# Mech_Interface_Starboard.net
KiCad netlist of a schematic drawn in Altium Designer
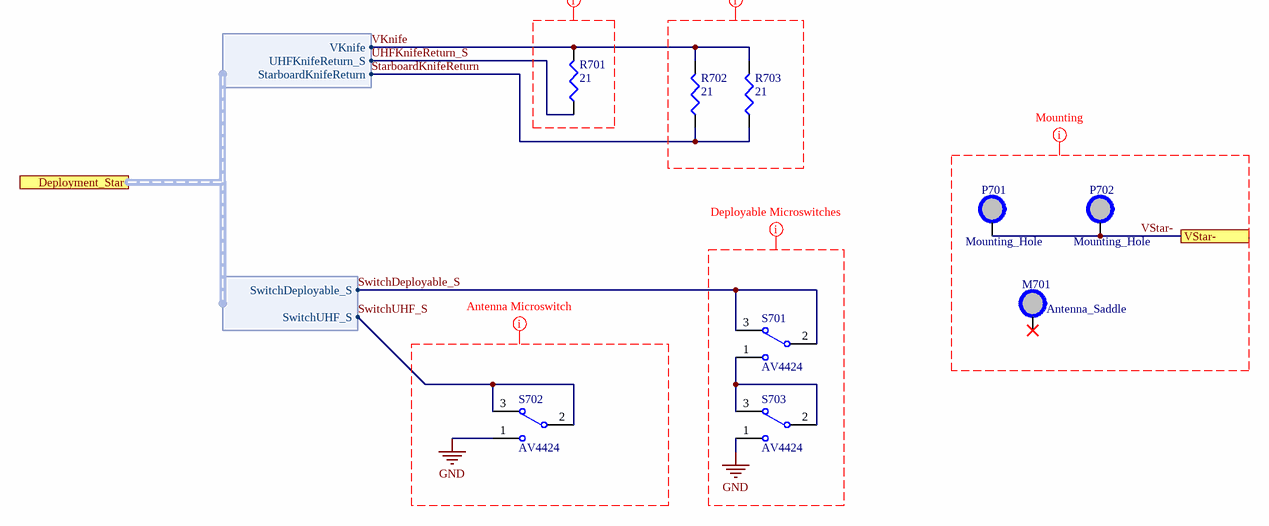
[diagram p0: Mech_Interface_Starboard.SchDoc]

(export (version "E")
  (design (tool "Eeschema 10.0.6"))
  (components
    (comp (ref "M701")
      (value "Antenna_Saddle")
      (footprint "ANTENNA_SADDLE")
      (fields
        (field (name "PART NUMBER") "PXX-ABS-00001")
        (field (name "MANUFACTURER PART NUMBER") "Custom")
        (field (name "PUBLISHER") "AlbertaSat")
      )
      (libsource (lib "Database") (part "Mounting_Hole"))
    )
    (comp (ref "P701")
      (value "Mounting_Hole")
      (footprint "DEPHINGE_MOUNTING_HOLE_BODY")
      (fields
        (field (name "PART NUMBER") "PXX-ABS-00004")
        (field (name "MANUFACTURER PART NUMBER") "Custom")
        (field (name "PUBLISHER") "AlbertaSat")
      )
      (libsource (lib "Database") (part "Mounting_Hole"))
    )
    (comp (ref "P702")
      (value "Mounting_Hole")
      (footprint "DEPHINGE_MOUNTING_HOLE_BODY")
      (fields
        (field (name "PART NUMBER") "PXX-ABS-00004")
        (field (name "MANUFACTURER PART NUMBER") "Custom")
        (field (name "PUBLISHER") "AlbertaSat")
      )
      (libsource (lib "Database") (part "Mounting_Hole"))
    )
    (comp (ref "R701")
      (value "21")
      (footprint "VSH-CPF1")
      (description "21 Ohms ±1% 1W Through Hole Resistor Axial Flame Proof, Moisture Resistant, Safety Metal Film")
      (fields
        (field (name "PART NUMBER") "PR-VSH-00317")
        (field (name "MANUFACTURER PART NUMBER") "CPF121R000FKEE6")
        (field (name "PUBLISHER") "AlbertaSat")
      )
      (libsource (lib "Database") (part "Res3"))
    )
    (comp (ref "R702")
      (value "21")
      (footprint "VSH-CPF1")
      (description "21 Ohms ±1% 1W Through Hole Resistor Axial Flame Proof, Moisture Resistant, Safety Metal Film")
      (fields
        (field (name "PART NUMBER") "PR-VSH-00317")
        (field (name "MANUFACTURER PART NUMBER") "CPF121R000FKEE6")
        (field (name "PUBLISHER") "AlbertaSat")
      )
      (libsource (lib "Database") (part "Res3"))
    )
    (comp (ref "R703")
      (value "21")
      (footprint "VSH-CPF1")
      (description "21 Ohms ±1% 1W Through Hole Resistor Axial Flame Proof, Moisture Resistant, Safety Metal Film")
      (fields
        (field (name "PART NUMBER") "PR-VSH-00317")
        (field (name "MANUFACTURER PART NUMBER") "CPF121R000FKEE6")
        (field (name "PUBLISHER") "AlbertaSat")
      )
      (libsource (lib "Database") (part "Res3"))
    )
    (comp (ref "S701")
      (value "AV4424")
      (footprint "PANA-AV4424")
      (description "SWITCH SNAP ACT SPDT 500MA 30V")
      (fields (field (name "PART NUMBER") "20035"))
      (libsource (lib "Database") (part "SW-SPDT"))
    )
    (comp (ref "S702")
      (value "AV4424")
      (footprint "PANA-AV4424")
      (description "SWITCH SNAP ACT SPDT 500MA 30V")
      (fields (field (name "PART NUMBER") "20035"))
      (libsource (lib "Database") (part "SW-SPDT"))
    )
    (comp (ref "S703")
      (value "AV4424")
      (footprint "PANA-AV4424")
      (description "SWITCH SNAP ACT SPDT 500MA 30V")
      (fields (field (name "PART NUMBER") "20035"))
      (libsource (lib "Database") (part "SW-SPDT"))
    )
  )
  (nets
    (net (code "2") (name "/StarboardKnifeReturn") (class "Default")
      (node (ref "R702") (pin "1") (pinfunction "1_1") (pintype "passive"))
      (node (ref "R703") (pin "1") (pinfunction "1_1") (pintype "passive"))
    )
    (net (code "3") (name "/SwitchDeployable_S") (class "Default")
      (node (ref "S701") (pin "2") (pinfunction "COM_2") (pintype "passive"))
      (node (ref "S701") (pin "3") (pinfunction "NC_3") (pintype "passive"))
    )
    (net (code "4") (name "/SwitchUHF_S") (class "Default")
      (node (ref "S702") (pin "2") (pinfunction "COM_2") (pintype "passive"))
      (node (ref "S702") (pin "3") (pinfunction "NC_3") (pintype "passive"))
    )
    (net (code "5") (name "/UHFKnifeReturn_S") (class "Default")
      (node (ref "R701") (pin "1") (pinfunction "1_1") (pintype "passive"))
    )
    (net (code "6") (name "/VKnife") (class "Default")
      (node (ref "R701") (pin "2") (pinfunction "2_2") (pintype "passive"))
      (node (ref "R702") (pin "2") (pinfunction "2_2") (pintype "passive"))
      (node (ref "R703") (pin "2") (pinfunction "2_2") (pintype "passive"))
    )
    (net (code "7") (name "/VStar-") (class "Default")
      (node (ref "P701") (pin "1") (pinfunction "0_1") (pintype "passive"))
      (node (ref "P702") (pin "1") (pinfunction "0_1") (pintype "passive"))
    )
    (net (code "9") (name "GND") (class "Default")
      (node (ref "S702") (pin "1") (pinfunction "NO_1") (pintype "passive"))
      (node (ref "S703") (pin "1") (pinfunction "NO_1") (pintype "passive"))
    )
    (net (code "10") (name "Net-(S701-NO)") (class "Default")
      (node (ref "S701") (pin "1") (pinfunction "NO_1") (pintype "passive"))
      (node (ref "S703") (pin "2") (pinfunction "COM_2") (pintype "passive"))
      (node (ref "S703") (pin "3") (pinfunction "NC_3") (pintype "passive"))
    )
    (net (code "11") (name "unconnected-(M701-0-Pad1)") (class "Default")
      (node (ref "M701") (pin "1") (pinfunction "0_1") (pintype "passive+no_connect"))
    )
  )
)
